# board.net
KiCad netlist of a schematic drawn in EAGLE
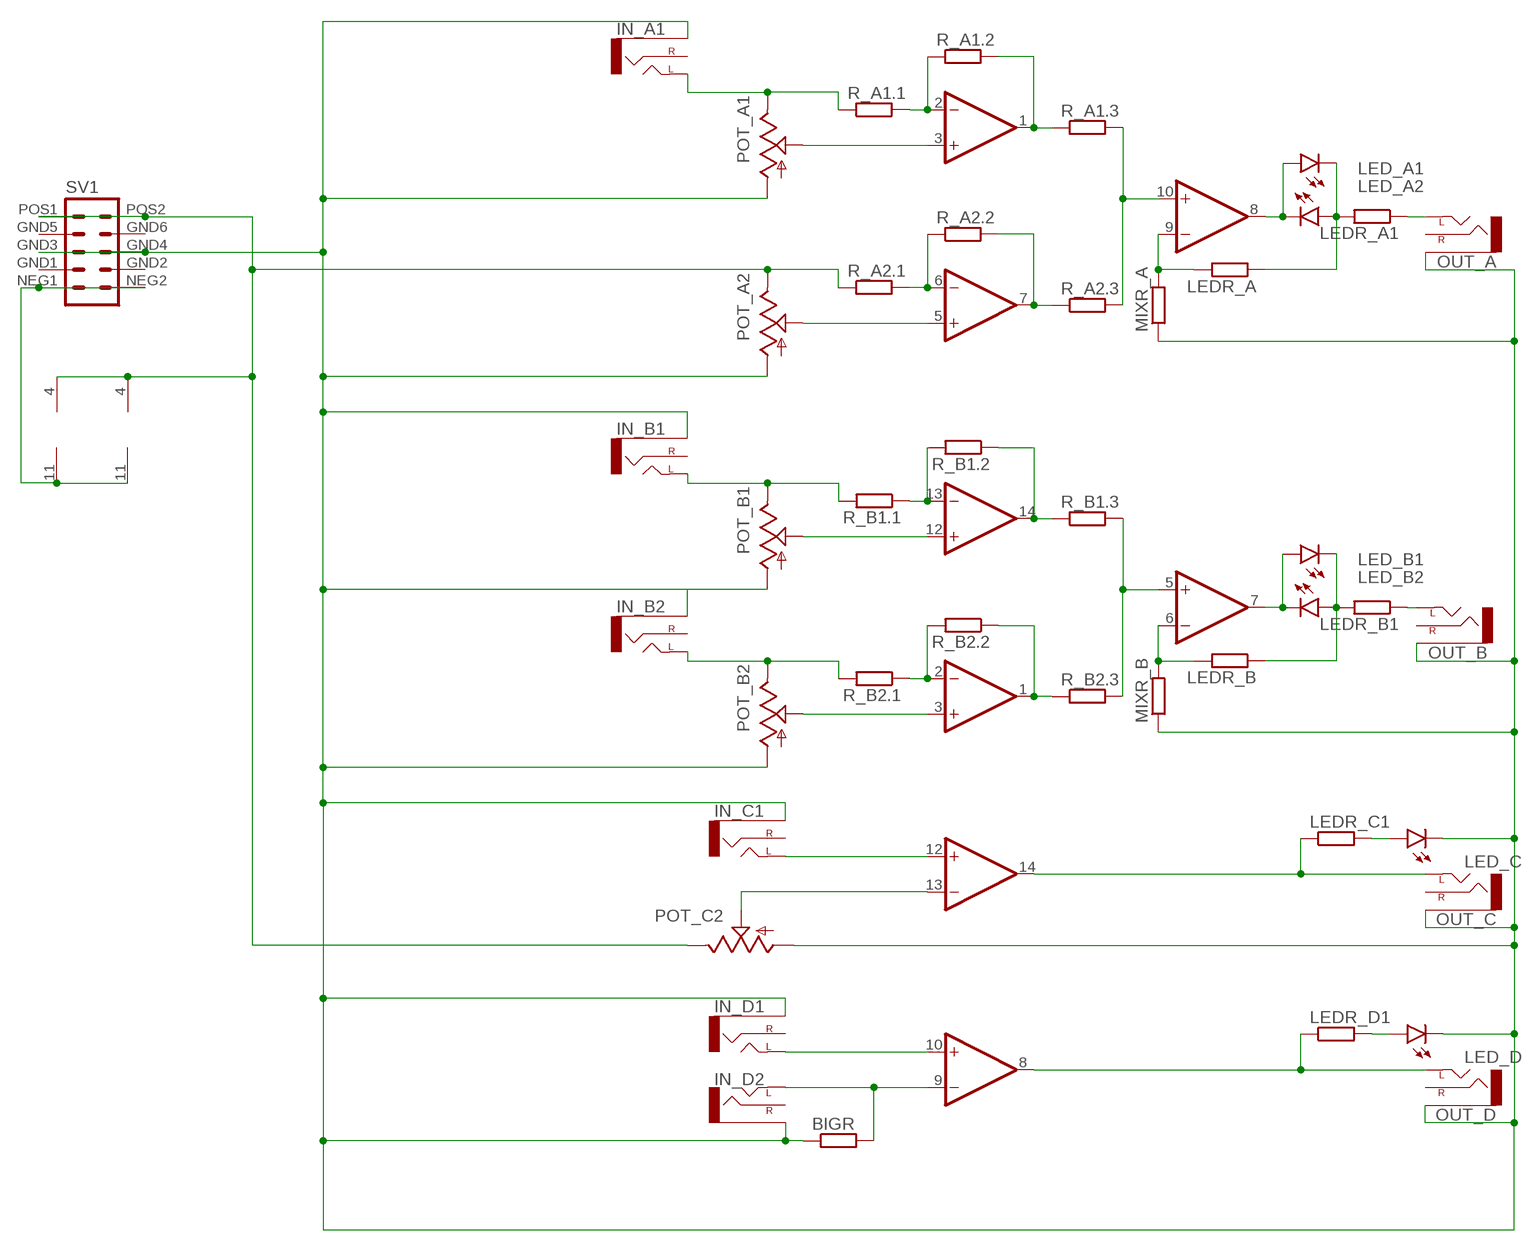
[diagram p0: schematic, sheet 1]

(export (version "E")
  (design (tool "Eeschema 10.0.6"))
  (components
    (comp (ref "BIGR")
      (value "RESISTOR7MM")
      (footprint "eagle-import:7MM_RESISTOR")
      (libsource (lib "eagle-import") (part "RESISTOR7MM"))
    )
    (comp (ref "IC1")
      (value "TL074P")
      (footprint "eagle-import:DIL14")
      (libsource (lib "eagle-import") (part "TL074P"))
    )
    (comp (ref "IC2")
      (value "TL074P")
      (footprint "eagle-import:DIL14")
      (libsource (lib "eagle-import") (part "TL074P"))
    )
    (comp (ref "IN_A1")
      (value "THONKI-STEREO")
      (footprint "eagle-import:WQP-PJ366ST_JACK")
      (libsource (lib "eagle-import") (part "THONKI-STEREO"))
    )
    (comp (ref "IN_B1")
      (value "THONKI-STEREO")
      (footprint "eagle-import:WQP-PJ366ST_JACK")
      (libsource (lib "eagle-import") (part "THONKI-STEREO"))
    )
    (comp (ref "IN_B2")
      (value "THONKI-STEREO")
      (footprint "eagle-import:WQP-PJ366ST_JACK")
      (libsource (lib "eagle-import") (part "THONKI-STEREO"))
    )
    (comp (ref "IN_C1")
      (value "THONKI-STEREO")
      (footprint "eagle-import:WQP-PJ366ST_JACK")
      (libsource (lib "eagle-import") (part "THONKI-STEREO"))
    )
    (comp (ref "IN_D1")
      (value "THONKI-STEREO")
      (footprint "eagle-import:WQP-PJ366ST_JACK")
      (libsource (lib "eagle-import") (part "THONKI-STEREO"))
    )
    (comp (ref "IN_D2")
      (value "THONKI-STEREO")
      (footprint "eagle-import:WQP-PJ366ST_JACK")
      (libsource (lib "eagle-import") (part "THONKI-STEREO"))
    )
    (comp (ref "LEDR_A")
      (value "RESISTOR7MM")
      (footprint "eagle-import:7MM_RESISTOR")
      (libsource (lib "eagle-import") (part "RESISTOR7MM"))
    )
    (comp (ref "LEDR_A1")
      (value "RESISTOR7MM")
      (footprint "eagle-import:7MM_RESISTOR")
      (libsource (lib "eagle-import") (part "RESISTOR7MM"))
    )
    (comp (ref "LEDR_B")
      (value "RESISTOR7MM")
      (footprint "eagle-import:7MM_RESISTOR")
      (libsource (lib "eagle-import") (part "RESISTOR7MM"))
    )
    (comp (ref "LEDR_B1")
      (value "RESISTOR7MM")
      (footprint "eagle-import:7MM_RESISTOR")
      (libsource (lib "eagle-import") (part "RESISTOR7MM"))
    )
    (comp (ref "LEDR_C1")
      (value "RESISTOR7MM")
      (footprint "eagle-import:7MM_RESISTOR")
      (libsource (lib "eagle-import") (part "RESISTOR7MM"))
    )
    (comp (ref "LEDR_D1")
      (value "RESISTOR7MM")
      (footprint "eagle-import:7MM_RESISTOR")
      (libsource (lib "eagle-import") (part "RESISTOR7MM"))
    )
    (comp (ref "LED_A1")
      (value "LED3MM")
      (footprint "eagle-import:LED_3MM")
      (libsource (lib "eagle-import") (part "LED3MM"))
    )
    (comp (ref "LED_A2")
      (value "LED3MM")
      (footprint "eagle-import:LED_3MM")
      (libsource (lib "eagle-import") (part "LED3MM"))
    )
    (comp (ref "LED_B1")
      (value "LED3MM")
      (footprint "eagle-import:LED_3MM")
      (libsource (lib "eagle-import") (part "LED3MM"))
    )
    (comp (ref "LED_B2")
      (value "LED3MM")
      (footprint "eagle-import:LED_3MM")
      (libsource (lib "eagle-import") (part "LED3MM"))
    )
    (comp (ref "LED_C")
      (value "LED3MM")
      (footprint "eagle-import:LED_3MM")
      (libsource (lib "eagle-import") (part "LED3MM"))
    )
    (comp (ref "LED_D")
      (value "LED3MM")
      (footprint "eagle-import:LED_3MM")
      (libsource (lib "eagle-import") (part "LED3MM"))
    )
    (comp (ref "MIXR_A")
      (value "RESISTOR7MM")
      (footprint "eagle-import:7MM_RESISTOR")
      (libsource (lib "eagle-import") (part "RESISTOR7MM"))
    )
    (comp (ref "MIXR_B")
      (value "RESISTOR7MM")
      (footprint "eagle-import:7MM_RESISTOR")
      (libsource (lib "eagle-import") (part "RESISTOR7MM"))
    )
    (comp (ref "OUT_A")
      (value "THONKI-STEREO")
      (footprint "eagle-import:WQP-PJ366ST_JACK")
      (libsource (lib "eagle-import") (part "THONKI-STEREO"))
    )
    (comp (ref "OUT_B")
      (value "THONKI-STEREO")
      (footprint "eagle-import:WQP-PJ366ST_JACK")
      (libsource (lib "eagle-import") (part "THONKI-STEREO"))
    )
    (comp (ref "OUT_C")
      (value "THONKI-STEREO")
      (footprint "eagle-import:WQP-PJ366ST_JACK")
      (libsource (lib "eagle-import") (part "THONKI-STEREO"))
    )
    (comp (ref "OUT_D")
      (value "THONKI-STEREO")
      (footprint "eagle-import:WQP-PJ366ST_JACK")
      (libsource (lib "eagle-import") (part "THONKI-STEREO"))
    )
    (comp (ref "POT_A1")
      (value "9MM_SNAP-IN_POT_")
      (footprint "eagle-import:9MM_SNAP-IN_POT")
      (libsource (lib "eagle-import") (part "9MM_SNAP-IN_POT_"))
    )
    (comp (ref "POT_A2")
      (value "9MM_SNAP-IN_POT_")
      (footprint "eagle-import:9MM_SNAP-IN_POT")
      (libsource (lib "eagle-import") (part "9MM_SNAP-IN_POT_"))
    )
    (comp (ref "POT_B1")
      (value "9MM_SNAP-IN_POT_")
      (footprint "eagle-import:9MM_SNAP-IN_POT")
      (libsource (lib "eagle-import") (part "9MM_SNAP-IN_POT_"))
    )
    (comp (ref "POT_B2")
      (value "9MM_SNAP-IN_POT_")
      (footprint "eagle-import:9MM_SNAP-IN_POT")
      (libsource (lib "eagle-import") (part "9MM_SNAP-IN_POT_"))
    )
    (comp (ref "POT_C2")
      (value "9MM_SNAP-IN_POT_")
      (footprint "eagle-import:9MM_SNAP-IN_POT")
      (libsource (lib "eagle-import") (part "9MM_SNAP-IN_POT_"))
    )
    (comp (ref "R_A1.1")
      (value "RESISTOR7MM")
      (footprint "eagle-import:7MM_RESISTOR")
      (libsource (lib "eagle-import") (part "RESISTOR7MM"))
    )
    (comp (ref "R_A1.2")
      (value "RESISTOR7MM")
      (footprint "eagle-import:7MM_RESISTOR")
      (libsource (lib "eagle-import") (part "RESISTOR7MM"))
    )
    (comp (ref "R_A1.3")
      (value "RESISTOR7MM")
      (footprint "eagle-import:7MM_RESISTOR")
      (libsource (lib "eagle-import") (part "RESISTOR7MM"))
    )
    (comp (ref "R_A2.1")
      (value "RESISTOR7MM")
      (footprint "eagle-import:7MM_RESISTOR")
      (libsource (lib "eagle-import") (part "RESISTOR7MM"))
    )
    (comp (ref "R_A2.2")
      (value "RESISTOR7MM")
      (footprint "eagle-import:7MM_RESISTOR")
      (libsource (lib "eagle-import") (part "RESISTOR7MM"))
    )
    (comp (ref "R_A2.3")
      (value "RESISTOR7MM")
      (footprint "eagle-import:7MM_RESISTOR")
      (libsource (lib "eagle-import") (part "RESISTOR7MM"))
    )
    (comp (ref "R_B1.1")
      (value "RESISTOR7MM")
      (footprint "eagle-import:7MM_RESISTOR")
      (libsource (lib "eagle-import") (part "RESISTOR7MM"))
    )
    (comp (ref "R_B1.2")
      (value "RESISTOR7MM")
      (footprint "eagle-import:7MM_RESISTOR")
      (libsource (lib "eagle-import") (part "RESISTOR7MM"))
    )
    (comp (ref "R_B1.3")
      (value "RESISTOR7MM")
      (footprint "eagle-import:7MM_RESISTOR")
      (libsource (lib "eagle-import") (part "RESISTOR7MM"))
    )
    (comp (ref "R_B2.1")
      (value "RESISTOR7MM")
      (footprint "eagle-import:7MM_RESISTOR")
      (libsource (lib "eagle-import") (part "RESISTOR7MM"))
    )
    (comp (ref "R_B2.2")
      (value "RESISTOR7MM")
      (footprint "eagle-import:7MM_RESISTOR")
      (libsource (lib "eagle-import") (part "RESISTOR7MM"))
    )
    (comp (ref "R_B2.3")
      (value "RESISTOR7MM")
      (footprint "eagle-import:7MM_RESISTOR")
      (libsource (lib "eagle-import") (part "RESISTOR7MM"))
    )
    (comp (ref "SV1")
      (value "EURO_POWER_HEADERLOCK_PADS")
      (footprint "eagle-import:EURO_PWR_HEADER_LOCK")
      (libsource (lib "eagle-import") (part "EURO_POWER_HEADERLOCK_PADS"))
    )
  )
  (nets
    (net (code "1") (name "Net-(IC1A-+IN)") (class "Default")
      (node (ref "IC1") (pin "3") (pinfunction "+IN_3") (pintype "input"))
      (node (ref "POT_A1") (pin "2") (pinfunction "S_2") (pintype "passive"))
    )
    (net (code "2") (name "Net-(IC1A--IN)") (class "Default")
      (node (ref "IC1") (pin "2") (pinfunction "-IN_2") (pintype "input"))
      (node (ref "R_A1.1") (pin "2") (pinfunction "2_2") (pintype "passive"))
      (node (ref "R_A1.2") (pin "1") (pinfunction "1_1") (pintype "passive"))
    )
    (net (code "3") (name "Net-(IC1A-OUT)") (class "Default")
      (node (ref "IC1") (pin "1") (pinfunction "OUT_1") (pintype "output"))
      (node (ref "R_A1.2") (pin "2") (pinfunction "2_2") (pintype "passive"))
      (node (ref "R_A1.3") (pin "1") (pinfunction "1_1") (pintype "passive"))
    )
    (net (code "4") (name "Net-(IC1B-+IN)") (class "Default")
      (node (ref "IC1") (pin "5") (pinfunction "+IN_5") (pintype "input"))
      (node (ref "POT_A2") (pin "2") (pinfunction "S_2") (pintype "passive"))
    )
    (net (code "5") (name "Net-(IC1B--IN)") (class "Default")
      (node (ref "IC1") (pin "6") (pinfunction "-IN_6") (pintype "input"))
      (node (ref "R_A2.1") (pin "2") (pinfunction "2_2") (pintype "passive"))
      (node (ref "R_A2.2") (pin "1") (pinfunction "1_1") (pintype "passive"))
    )
    (net (code "6") (name "Net-(IC1B-OUT)") (class "Default")
      (node (ref "IC1") (pin "7") (pinfunction "OUT_7") (pintype "output"))
      (node (ref "R_A2.2") (pin "2") (pinfunction "2_2") (pintype "passive"))
      (node (ref "R_A2.3") (pin "1") (pinfunction "1_1") (pintype "passive"))
    )
    (net (code "7") (name "Net-(IC1C-+IN)") (class "Default")
      (node (ref "IC1") (pin "10") (pinfunction "+IN_10") (pintype "input"))
      (node (ref "R_A1.3") (pin "2") (pinfunction "2_2") (pintype "passive"))
      (node (ref "R_A2.3") (pin "2") (pinfunction "2_2") (pintype "passive"))
    )
    (net (code "8") (name "Net-(IC1C--IN)") (class "Default")
      (node (ref "IC1") (pin "9") (pinfunction "-IN_9") (pintype "input"))
      (node (ref "LEDR_A") (pin "2") (pinfunction "2_2") (pintype "passive"))
      (node (ref "MIXR_A") (pin "2") (pinfunction "2_2") (pintype "passive"))
    )
    (net (code "9") (name "Net-(IC1C-OUT)") (class "Default")
      (node (ref "IC1") (pin "8") (pinfunction "OUT_8") (pintype "output"))
      (node (ref "LED_A1") (pin "A") (pinfunction "A_A") (pintype "passive"))
      (node (ref "LED_A2") (pin "K") (pinfunction "C_K") (pintype "passive"))
    )
    (net (code "10") (name "Net-(IC1D-+IN)") (class "Default")
      (node (ref "IC1") (pin "12") (pinfunction "+IN_12") (pintype "input"))
      (node (ref "POT_B1") (pin "2") (pinfunction "S_2") (pintype "passive"))
    )
    (net (code "11") (name "Net-(IC1D--IN)") (class "Default")
      (node (ref "IC1") (pin "13") (pinfunction "-IN_13") (pintype "input"))
      (node (ref "R_B1.1") (pin "1") (pinfunction "1_1") (pintype "passive"))
      (node (ref "R_B1.2") (pin "2") (pinfunction "2_2") (pintype "passive"))
    )
    (net (code "12") (name "Net-(IC1D-OUT)") (class "Default")
      (node (ref "IC1") (pin "14") (pinfunction "OUT_14") (pintype "output"))
      (node (ref "R_B1.2") (pin "1") (pinfunction "1_1") (pintype "passive"))
      (node (ref "R_B1.3") (pin "1") (pinfunction "1_1") (pintype "passive"))
    )
    (net (code "13") (name "Net-(IC1E-V+)") (class "Default")
      (node (ref "IC1") (pin "4") (pinfunction "V+_4") (pintype "power_in"))
      (node (ref "IC2") (pin "4") (pinfunction "V+_4") (pintype "power_in"))
      (node (ref "POT_A2") (pin "3") (pinfunction "E_3") (pintype "passive"))
      (node (ref "POT_C2") (pin "3") (pinfunction "E_3") (pintype "passive"))
      (node (ref "R_A2.1") (pin "1") (pinfunction "1_1") (pintype "passive"))
      (node (ref "SV1") (pin "POS1") (pinfunction "10_POS1") (pintype "passive"))
      (node (ref "SV1") (pin "POS2") (pinfunction "9_POS2") (pintype "passive"))
    )
    (net (code "14") (name "Net-(IC1E-V-)") (class "Default")
      (node (ref "IC1") (pin "11") (pinfunction "V-_11") (pintype "power_in"))
      (node (ref "IC2") (pin "11") (pinfunction "V-_11") (pintype "power_in"))
      (node (ref "SV1") (pin "NEG1") (pinfunction "2_NEG1") (pintype "passive"))
      (node (ref "SV1") (pin "NEG2") (pinfunction "1_NEG2") (pintype "passive"))
    )
    (net (code "15") (name "Net-(IC2A-+IN)") (class "Default")
      (node (ref "IC2") (pin "3") (pinfunction "+IN_3") (pintype "input"))
      (node (ref "POT_B2") (pin "2") (pinfunction "S_2") (pintype "passive"))
    )
    (net (code "16") (name "Net-(IC2A--IN)") (class "Default")
      (node (ref "IC2") (pin "2") (pinfunction "-IN_2") (pintype "input"))
      (node (ref "R_B2.1") (pin "1") (pinfunction "1_1") (pintype "passive"))
      (node (ref "R_B2.2") (pin "2") (pinfunction "2_2") (pintype "passive"))
    )
    (net (code "17") (name "Net-(IC2A-OUT)") (class "Default")
      (node (ref "IC2") (pin "1") (pinfunction "OUT_1") (pintype "output"))
      (node (ref "R_B2.2") (pin "1") (pinfunction "1_1") (pintype "passive"))
      (node (ref "R_B2.3") (pin "1") (pinfunction "1_1") (pintype "passive"))
    )
    (net (code "18") (name "Net-(IC2B-+IN)") (class "Default")
      (node (ref "IC2") (pin "5") (pinfunction "+IN_5") (pintype "input"))
      (node (ref "R_B1.3") (pin "2") (pinfunction "2_2") (pintype "passive"))
      (node (ref "R_B2.3") (pin "2") (pinfunction "2_2") (pintype "passive"))
    )
    (net (code "19") (name "Net-(IC2B--IN)") (class "Default")
      (node (ref "IC2") (pin "6") (pinfunction "-IN_6") (pintype "input"))
      (node (ref "LEDR_B") (pin "2") (pinfunction "2_2") (pintype "passive"))
      (node (ref "MIXR_B") (pin "2") (pinfunction "2_2") (pintype "passive"))
    )
    (net (code "20") (name "Net-(IC2B-OUT)") (class "Default")
      (node (ref "IC2") (pin "7") (pinfunction "OUT_7") (pintype "output"))
      (node (ref "LED_B1") (pin "A") (pinfunction "A_A") (pintype "passive"))
      (node (ref "LED_B2") (pin "K") (pinfunction "C_K") (pintype "passive"))
    )
    (net (code "21") (name "Net-(IC2C-+IN)") (class "Default")
      (node (ref "IC2") (pin "10") (pinfunction "+IN_10") (pintype "input"))
      (node (ref "IN_D1") (pin "P$1_TIP") (pinfunction "LEFT_P$1_TIP") (pintype "bidirectional"))
    )
    (net (code "22") (name "Net-(IC2C--IN)") (class "Default")
      (node (ref "BIGR") (pin "2") (pinfunction "2_2") (pintype "passive"))
      (node (ref "IC2") (pin "9") (pinfunction "-IN_9") (pintype "input"))
      (node (ref "IN_D2") (pin "P$1_TIP") (pinfunction "LEFT_P$1_TIP") (pintype "bidirectional"))
    )
    (net (code "23") (name "Net-(IC2C-OUT)") (class "Default")
      (node (ref "IC2") (pin "8") (pinfunction "OUT_8") (pintype "output"))
      (node (ref "LEDR_D1") (pin "1") (pinfunction "1_1") (pintype "passive"))
      (node (ref "OUT_D") (pin "P$1_TIP") (pinfunction "LEFT_P$1_TIP") (pintype "bidirectional"))
    )
    (net (code "24") (name "Net-(IC2D-+IN)") (class "Default")
      (node (ref "IC2") (pin "12") (pinfunction "+IN_12") (pintype "input"))
      (node (ref "IN_C1") (pin "P$1_TIP") (pinfunction "LEFT_P$1_TIP") (pintype "bidirectional"))
    )
    (net (code "25") (name "Net-(IC2D--IN)") (class "Default")
      (node (ref "IC2") (pin "13") (pinfunction "-IN_13") (pintype "input"))
      (node (ref "POT_C2") (pin "2") (pinfunction "S_2") (pintype "passive"))
    )
    (net (code "26") (name "Net-(IC2D-OUT)") (class "Default")
      (node (ref "IC2") (pin "14") (pinfunction "OUT_14") (pintype "output"))
      (node (ref "LEDR_C1") (pin "1") (pinfunction "1_1") (pintype "passive"))
      (node (ref "OUT_C") (pin "P$1_TIP") (pinfunction "LEFT_P$1_TIP") (pintype "bidirectional"))
    )
    (net (code "27") (name "Net-(IN_A1-LEFT)") (class "Default")
      (node (ref "IN_A1") (pin "P$1_TIP") (pinfunction "LEFT_P$1_TIP") (pintype "bidirectional"))
      (node (ref "POT_A1") (pin "3") (pinfunction "E_3") (pintype "passive"))
      (node (ref "R_A1.1") (pin "1") (pinfunction "1_1") (pintype "passive"))
    )
    (net (code "28") (name "Net-(IN_A1-SLEEVE)") (class "Default")
      (node (ref "BIGR") (pin "1") (pinfunction "1_1") (pintype "passive"))
      (node (ref "IN_A1") (pin "P$3_SLEEVE") (pinfunction "SLEEVE_P$3_SLEEVE") (pintype "bidirectional"))
      (node (ref "IN_B1") (pin "P$3_SLEEVE") (pinfunction "SLEEVE_P$3_SLEEVE") (pintype "bidirectional"))
      (node (ref "IN_B2") (pin "P$3_SLEEVE") (pinfunction "SLEEVE_P$3_SLEEVE") (pintype "bidirectional"))
      (node (ref "IN_C1") (pin "P$3_SLEEVE") (pinfunction "SLEEVE_P$3_SLEEVE") (pintype "bidirectional"))
      (node (ref "IN_D1") (pin "P$3_SLEEVE") (pinfunction "SLEEVE_P$3_SLEEVE") (pintype "bidirectional"))
      (node (ref "IN_D2") (pin "P$3_SLEEVE") (pinfunction "SLEEVE_P$3_SLEEVE") (pintype "bidirectional"))
      (node (ref "LED_C") (pin "K") (pinfunction "C_K") (pintype "passive"))
      (node (ref "LED_D") (pin "K") (pinfunction "C_K") (pintype "passive"))
      (node (ref "MIXR_A") (pin "1") (pinfunction "1_1") (pintype "passive"))
      (node (ref "MIXR_B") (pin "1") (pinfunction "1_1") (pintype "passive"))
      (node (ref "OUT_A") (pin "P$3_SLEEVE") (pinfunction "SLEEVE_P$3_SLEEVE") (pintype "bidirectional"))
      (node (ref "OUT_B") (pin "P$3_SLEEVE") (pinfunction "SLEEVE_P$3_SLEEVE") (pintype "bidirectional"))
      (node (ref "OUT_C") (pin "P$3_SLEEVE") (pinfunction "SLEEVE_P$3_SLEEVE") (pintype "bidirectional"))
      (node (ref "OUT_D") (pin "P$3_SLEEVE") (pinfunction "SLEEVE_P$3_SLEEVE") (pintype "bidirectional"))
      (node (ref "POT_A1") (pin "1") (pinfunction "A_1") (pintype "passive"))
      (node (ref "POT_A2") (pin "1") (pinfunction "A_1") (pintype "passive"))
      (node (ref "POT_B1") (pin "1") (pinfunction "A_1") (pintype "passive"))
      (node (ref "POT_B2") (pin "1") (pinfunction "A_1") (pintype "passive"))
      (node (ref "POT_C2") (pin "1") (pinfunction "A_1") (pintype "passive"))
      (node (ref "SV1") (pin "GND3") (pinfunction "6_GND3") (pintype "passive"))
      (node (ref "SV1") (pin "GND4") (pinfunction "5_GND4") (pintype "passive"))
    )
    (net (code "29") (name "Net-(IN_B1-LEFT)") (class "Default")
      (node (ref "IN_B1") (pin "P$1_TIP") (pinfunction "LEFT_P$1_TIP") (pintype "bidirectional"))
      (node (ref "POT_B1") (pin "3") (pinfunction "E_3") (pintype "passive"))
      (node (ref "R_B1.1") (pin "2") (pinfunction "2_2") (pintype "passive"))
    )
    (net (code "30") (name "Net-(IN_B2-LEFT)") (class "Default")
      (node (ref "IN_B2") (pin "P$1_TIP") (pinfunction "LEFT_P$1_TIP") (pintype "bidirectional"))
      (node (ref "POT_B2") (pin "3") (pinfunction "E_3") (pintype "passive"))
      (node (ref "R_B2.1") (pin "2") (pinfunction "2_2") (pintype "passive"))
    )
    (net (code "31") (name "Net-(LEDR_C1-Pad2)") (class "Default")
      (node (ref "LEDR_C1") (pin "2") (pinfunction "2_2") (pintype "passive"))
      (node (ref "LED_C") (pin "A") (pinfunction "A_A") (pintype "passive"))
    )
    (net (code "32") (name "Net-(LEDR_D1-Pad2)") (class "Default")
      (node (ref "LEDR_D1") (pin "2") (pinfunction "2_2") (pintype "passive"))
      (node (ref "LED_D") (pin "A") (pinfunction "A_A") (pintype "passive"))
    )
    (net (code "33") (name "Net-(LED_A1-C)") (class "Default")
      (node (ref "LEDR_A") (pin "1") (pinfunction "1_1") (pintype "passive"))
      (node (ref "LEDR_A1") (pin "2") (pinfunction "2_2") (pintype "passive"))
      (node (ref "LED_A1") (pin "K") (pinfunction "C_K") (pintype "passive"))
      (node (ref "LED_A2") (pin "A") (pinfunction "A_A") (pintype "passive"))
    )
    (net (code "34") (name "Net-(LED_B1-C)") (class "Default")
      (node (ref "LEDR_B") (pin "1") (pinfunction "1_1") (pintype "passive"))
      (node (ref "LEDR_B1") (pin "2") (pinfunction "2_2") (pintype "passive"))
      (node (ref "LED_B1") (pin "K") (pinfunction "C_K") (pintype "passive"))
      (node (ref "LED_B2") (pin "A") (pinfunction "A_A") (pintype "passive"))
    )
    (net (code "35") (name "Net-(OUT_A-LEFT)") (class "Default")
      (node (ref "LEDR_A1") (pin "1") (pinfunction "1_1") (pintype "passive"))
      (node (ref "OUT_A") (pin "P$1_TIP") (pinfunction "LEFT_P$1_TIP") (pintype "bidirectional"))
    )
    (net (code "36") (name "Net-(OUT_B-LEFT)") (class "Default")
      (node (ref "LEDR_B1") (pin "1") (pinfunction "1_1") (pintype "passive"))
      (node (ref "OUT_B") (pin "P$1_TIP") (pinfunction "LEFT_P$1_TIP") (pintype "bidirectional"))
    )
    (net (code "37") (name "unconnected-(IN_A1-RIGHT-PadP$2_SWITCH)") (class "Default")
      (node (ref "IN_A1") (pin "P$2_SWITCH") (pinfunction "RIGHT_P$2_SWITCH") (pintype "bidirectional"))
    )
    (net (code "38") (name "unconnected-(IN_B1-RIGHT-PadP$2_SWITCH)") (class "Default")
      (node (ref "IN_B1") (pin "P$2_SWITCH") (pinfunction "RIGHT_P$2_SWITCH") (pintype "bidirectional"))
    )
    (net (code "39") (name "unconnected-(IN_B2-RIGHT-PadP$2_SWITCH)") (class "Default")
      (node (ref "IN_B2") (pin "P$2_SWITCH") (pinfunction "RIGHT_P$2_SWITCH") (pintype "bidirectional"))
    )
    (net (code "40") (name "unconnected-(IN_C1-RIGHT-PadP$2_SWITCH)") (class "Default")
      (node (ref "IN_C1") (pin "P$2_SWITCH") (pinfunction "RIGHT_P$2_SWITCH") (pintype "bidirectional"))
    )
    (net (code "41") (name "unconnected-(IN_D1-RIGHT-PadP$2_SWITCH)") (class "Default")
      (node (ref "IN_D1") (pin "P$2_SWITCH") (pinfunction "RIGHT_P$2_SWITCH") (pintype "bidirectional"))
    )
    (net (code "42") (name "unconnected-(IN_D2-RIGHT-PadP$2_SWITCH)") (class "Default")
      (node (ref "IN_D2") (pin "P$2_SWITCH") (pinfunction "RIGHT_P$2_SWITCH") (pintype "bidirectional"))
    )
    (net (code "43") (name "unconnected-(OUT_A-RIGHT-PadP$2_SWITCH)") (class "Default")
      (node (ref "OUT_A") (pin "P$2_SWITCH") (pinfunction "RIGHT_P$2_SWITCH") (pintype "bidirectional"))
    )
    (net (code "44") (name "unconnected-(OUT_B-RIGHT-PadP$2_SWITCH)") (class "Default")
      (node (ref "OUT_B") (pin "P$2_SWITCH") (pinfunction "RIGHT_P$2_SWITCH") (pintype "bidirectional"))
    )
    (net (code "45") (name "unconnected-(OUT_C-RIGHT-PadP$2_SWITCH)") (class "Default")
      (node (ref "OUT_C") (pin "P$2_SWITCH") (pinfunction "RIGHT_P$2_SWITCH") (pintype "bidirectional"))
    )
    (net (code "46") (name "unconnected-(OUT_D-RIGHT-PadP$2_SWITCH)") (class "Default")
      (node (ref "OUT_D") (pin "P$2_SWITCH") (pinfunction "RIGHT_P$2_SWITCH") (pintype "bidirectional"))
    )
    (net (code "47") (name "unconnected-(SV1-3-PadGND2)") (class "Default")
      (node (ref "SV1") (pin "GND2") (pinfunction "3_GND2") (pintype "passive"))
    )
    (net (code "48") (name "unconnected-(SV1-4-PadGND1)") (class "Default")
      (node (ref "SV1") (pin "GND1") (pinfunction "4_GND1") (pintype "passive"))
    )
    (net (code "49") (name "unconnected-(SV1-7-PadGND6)") (class "Default")
      (node (ref "SV1") (pin "GND6") (pinfunction "7_GND6") (pintype "passive"))
    )
    (net (code "50") (name "unconnected-(SV1-8-PadGND5)") (class "Default")
      (node (ref "SV1") (pin "GND5") (pinfunction "8_GND5") (pintype "passive"))
    )
  )
)
